# fpga-power-outside.net
KiCad netlist of a schematic drawn in Altium Designer
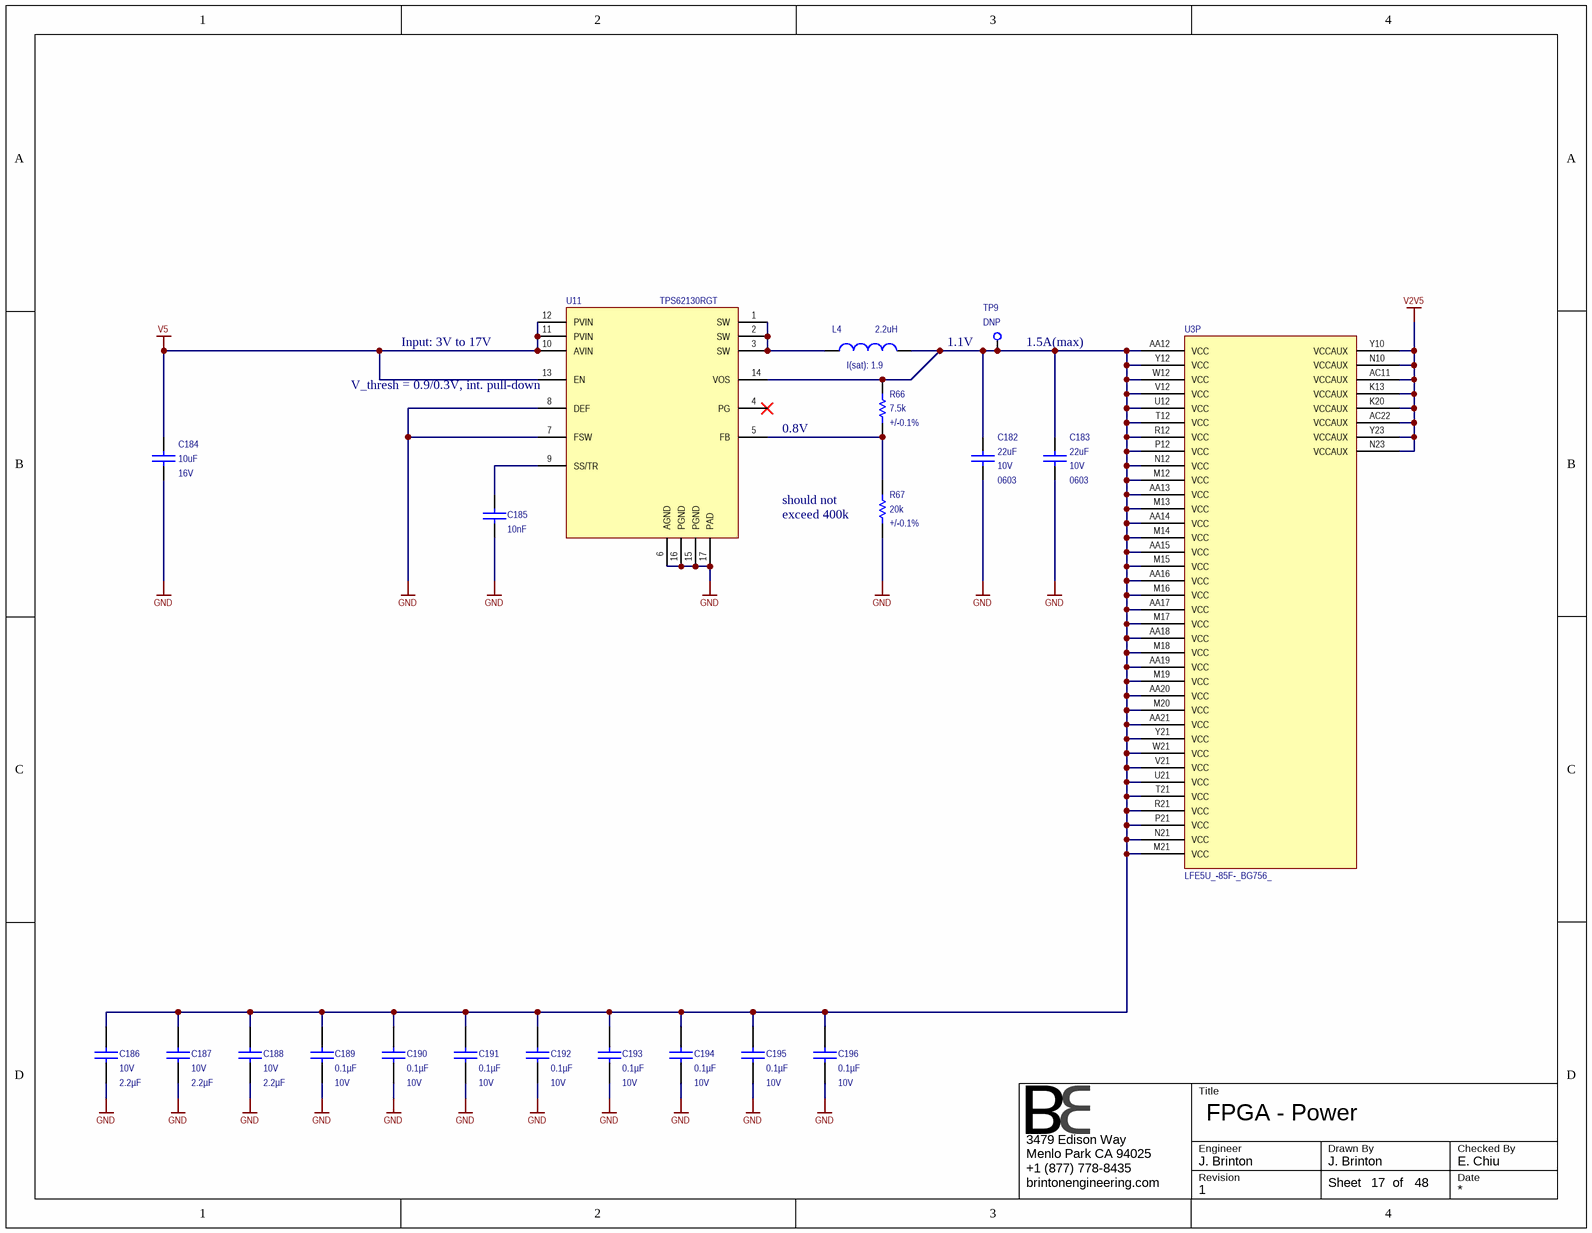
[diagram p0: fpga-power-outside.SchDoc]

(export (version "E")
  (design (tool "Eeschema 10.0.6"))
  (components
    (comp (ref "C182")
      (value "22uF")
      (footprint "0603")
      (description "Ceramic Capacitor 22uF +/-20% 10V X5R SMD 0603")
      (fields
        (field (name "MANUFACTURER") "TDK Corporation")
        (field (name "TOLERANCE") "+/-20%")
        (field (name "VOLTAGE") "10V")
      )
      (libsource (lib "generic") (part "CAP"))
    )
    (comp (ref "C183")
      (value "22uF")
      (footprint "0603")
      (description "Ceramic Capacitor 22uF +/-20% 10V X5R SMD 0603")
      (fields
        (field (name "MANUFACTURER") "TDK Corporation")
        (field (name "TOLERANCE") "+/-20%")
        (field (name "VOLTAGE") "10V")
      )
      (libsource (lib "generic") (part "CAP"))
    )
    (comp (ref "C184")
      (value "10uF")
      (footprint "0603")
      (description "Ceramic Capacitor 10uF +/-20% 16V X5R 0603")
      (fields
        (field (name "MANUFACTURER") "Taiyo Yuden")
        (field (name "VOLTAGE") "16V")
        (field (name "Comment") "CAP 10UF 0603")
      )
      (libsource (lib "") (part "CAP_1"))
    )
    (comp (ref "C185")
      (value "10nF")
      (footprint "0201")
      (description "Ceramic Capacitor 10nF +/-10% 10V X5R 0201")
      (fields (field (name "MANUFACTURER") "TDK Corporation") (field (name "VOLTAGE") "10V"))
      (libsource (lib "") (part "CAP_1"))
    )
    (comp (ref "C186")
      (value "GRM188R71A225KE15D")
      (footprint "CAPC1608X90N")
      (description "CAP CER 2.2UF 10V 10% X7R 0603")
      (fields
        (field (name "MANUFACTURER") "Murata Electronics North America")
        (field (name "TOLERANCE") "±10%")
        (field (name "VOLTAGE - RATED") "10V")
        (field (name "CAPACITANCE") "2.2µF")
      )
      (libsource (lib "murata") (part "GRM188R71A225KE15D"))
    )
    (comp (ref "C187")
      (value "GRM188R71A225KE15D")
      (footprint "CAPC1608X90N")
      (description "CAP CER 2.2UF 10V 10% X7R 0603")
      (fields
        (field (name "MANUFACTURER") "Murata Electronics North America")
        (field (name "TOLERANCE") "±10%")
        (field (name "VOLTAGE - RATED") "10V")
        (field (name "CAPACITANCE") "2.2µF")
      )
      (libsource (lib "murata") (part "GRM188R71A225KE15D"))
    )
    (comp (ref "C188")
      (value "GRM188R71A225KE15D")
      (footprint "CAPC1608X90N")
      (description "CAP CER 2.2UF 10V 10% X7R 0603")
      (fields
        (field (name "MANUFACTURER") "Murata Electronics North America")
        (field (name "TOLERANCE") "±10%")
        (field (name "VOLTAGE - RATED") "10V")
        (field (name "CAPACITANCE") "2.2µF")
      )
      (libsource (lib "murata") (part "GRM188R71A225KE15D"))
    )
    (comp (ref "C189")
      (value "GRM155R71A104KA01J")
      (footprint "CAPC1005X56N")
      (description "CAP CER 0.1UF 10V 10% X7R 0402")
      (fields
        (field (name "MANUFACTURER") "Murata Electronics North America")
        (field (name "TOLERANCE") "±10%")
        (field (name "CAPACITANCE") "0.1µF")
        (field (name "VOLTAGE - RATED") "10V")
      )
      (libsource (lib "murata") (part "GRM155R71A104KA01J"))
    )
    (comp (ref "C190")
      (value "GRM155R71A104KA01J")
      (footprint "CAPC1005X56N")
      (description "CAP CER 0.1UF 10V 10% X7R 0402")
      (fields
        (field (name "MANUFACTURER") "Murata Electronics North America")
        (field (name "TOLERANCE") "±10%")
        (field (name "CAPACITANCE") "0.1µF")
        (field (name "VOLTAGE - RATED") "10V")
      )
      (libsource (lib "murata") (part "GRM155R71A104KA01J"))
    )
    (comp (ref "C191")
      (value "GRM155R71A104KA01J")
      (footprint "CAPC1005X56N")
      (description "CAP CER 0.1UF 10V 10% X7R 0402")
      (fields
        (field (name "MANUFACTURER") "Murata Electronics North America")
        (field (name "TOLERANCE") "±10%")
        (field (name "CAPACITANCE") "0.1µF")
        (field (name "VOLTAGE - RATED") "10V")
      )
      (libsource (lib "murata") (part "GRM155R71A104KA01J"))
    )
    (comp (ref "C192")
      (value "GRM155R71A104KA01J")
      (footprint "CAPC1005X56N")
      (description "CAP CER 0.1UF 10V 10% X7R 0402")
      (fields
        (field (name "MANUFACTURER") "Murata Electronics North America")
        (field (name "TOLERANCE") "±10%")
        (field (name "CAPACITANCE") "0.1µF")
        (field (name "VOLTAGE - RATED") "10V")
      )
      (libsource (lib "murata") (part "GRM155R71A104KA01J"))
    )
    (comp (ref "C193")
      (value "GRM155R71A104KA01J")
      (footprint "CAPC1005X56N")
      (description "CAP CER 0.1UF 10V 10% X7R 0402")
      (fields
        (field (name "MANUFACTURER") "Murata Electronics North America")
        (field (name "TOLERANCE") "±10%")
        (field (name "CAPACITANCE") "0.1µF")
        (field (name "VOLTAGE - RATED") "10V")
      )
      (libsource (lib "murata") (part "GRM155R71A104KA01J"))
    )
    (comp (ref "C194")
      (value "GRM155R71A104KA01J")
      (footprint "CAPC1005X56N")
      (description "CAP CER 0.1UF 10V 10% X7R 0402")
      (fields
        (field (name "MANUFACTURER") "Murata Electronics North America")
        (field (name "TOLERANCE") "±10%")
        (field (name "CAPACITANCE") "0.1µF")
        (field (name "VOLTAGE - RATED") "10V")
      )
      (libsource (lib "murata") (part "GRM155R71A104KA01J"))
    )
    (comp (ref "C195")
      (value "GRM155R71A104KA01J")
      (footprint "CAPC1005X56N")
      (description "CAP CER 0.1UF 10V 10% X7R 0402")
      (fields
        (field (name "MANUFACTURER") "Murata Electronics North America")
        (field (name "TOLERANCE") "±10%")
        (field (name "CAPACITANCE") "0.1µF")
        (field (name "VOLTAGE - RATED") "10V")
      )
      (libsource (lib "murata") (part "GRM155R71A104KA01J"))
    )
    (comp (ref "C196")
      (value "GRM155R71A104KA01J")
      (footprint "CAPC1005X56N")
      (description "CAP CER 0.1UF 10V 10% X7R 0402")
      (fields
        (field (name "MANUFACTURER") "Murata Electronics North America")
        (field (name "TOLERANCE") "±10%")
        (field (name "CAPACITANCE") "0.1µF")
        (field (name "VOLTAGE - RATED") "10V")
      )
      (libsource (lib "murata") (part "GRM155R71A104KA01J"))
    )
    (comp (ref "L4")
      (value "2.2uH")
      (footprint "ASPI-3010FS")
      (description "Wirewound Inductor 2.2uH +/-20% 1.9A SMD 2518")
      (fields
        (field (name "MANUFACTURER") "Abracon")
        (field (name "I(SAT)") "1.9")
        (field (name "Comment") "ASPI-0310FS-2R2M-T2")
      )
      (libsource (lib "CamBoard_Pico_70.19K") (part "COIL"))
    )
    (comp (ref "R66")
      (value "7.5k")
      (footprint "RESC1608X55N")
      (description "Thick Film Resistor 7.5k Ohms +/-0.1% 0.1W 75V SMD 0603")
      (fields
        (field (name "TOLERANCE") "+/-0.1%")
        (field (name "MANUFACTURER") "Panasonic - ECG")
        (field (name "VOLTAGE") "75V")
      )
      (libsource (lib "brinton") (part "RES"))
    )
    (comp (ref "R67")
      (value "20k")
      (footprint "RESC1608X55N")
      (description "Thick Film Resistor 20k Ohms +/-0.1% 0.1W 75V SMD 0603")
      (fields
        (field (name "TOLERANCE") "+/-0.1%")
        (field (name "MANUFACTURER") "Panasonic - ECG")
        (field (name "VOLTAGE") "75V")
      )
      (libsource (lib "brinton") (part "RES"))
    )
    (comp (ref "TP9")
      (value "TEST_POINT")
      (footprint "TEST_POINT")
      (description "Thruhole Miniature Test Point")
      (fields (field (name "MANUFACTURER") "Keystone Electronics Corp") (field (name "DO NOT PLACE") "DNP"))
      (libsource (lib "generic") (part "TEST_POINT"))
    )
    (comp (ref "U3")
      (value "LFE5U_-85F-_BG756_")
      (footprint "lattice:caBGA756")
      (description "ECP5 FPGA, 85k LUT, 756-caBGA")
      (fields (field (name "MANUFACTURER") "Lattice Semiconductor"))
      (libsource (lib "lattice") (part "LFE5U_-85F-_BG756_"))
    )
    (comp (ref "U11")
      (value "TPS62130RGT")
      (footprint "S-PQFP-8N")
      (description "3-17V 3A Step-Down Converter VQFN")
      (fields (field (name "MANUFACTURER") "Texas Instruments"))
      (libsource (lib "ti") (part "TPS62130RGT"))
    )
  )
  (nets
    (net (code "1") (name "GND") (class "Default")
      (node (ref "C182") (pin "1") (pinfunction "1_1") (pintype "passive"))
      (node (ref "C183") (pin "1") (pinfunction "1_1") (pintype "passive"))
      (node (ref "C184") (pin "1") (pinfunction "1_1") (pintype "passive"))
      (node (ref "C185") (pin "2") (pinfunction "2_2") (pintype "passive"))
      (node (ref "C186") (pin "1") (pinfunction "1_1") (pintype "passive"))
      (node (ref "C187") (pin "1") (pinfunction "1_1") (pintype "passive"))
      (node (ref "C188") (pin "1") (pinfunction "1_1") (pintype "passive"))
      (node (ref "C189") (pin "1") (pinfunction "1_1") (pintype "passive"))
      (node (ref "C190") (pin "1") (pinfunction "1_1") (pintype "passive"))
      (node (ref "C191") (pin "1") (pinfunction "1_1") (pintype "passive"))
      (node (ref "C192") (pin "1") (pinfunction "1_1") (pintype "passive"))
      (node (ref "C193") (pin "1") (pinfunction "1_1") (pintype "passive"))
      (node (ref "C194") (pin "1") (pinfunction "1_1") (pintype "passive"))
      (node (ref "C195") (pin "1") (pinfunction "1_1") (pintype "passive"))
      (node (ref "C196") (pin "1") (pinfunction "1_1") (pintype "passive"))
      (node (ref "R67") (pin "1") (pinfunction "1_1") (pintype "passive"))
      (node (ref "U11") (pin "15") (pinfunction "PGND_15") (pintype "passive"))
      (node (ref "U11") (pin "16") (pinfunction "PGND_16") (pintype "passive"))
      (node (ref "U11") (pin "17") (pinfunction "PAD_17") (pintype "passive"))
      (node (ref "U11") (pin "6") (pinfunction "AGND_6") (pintype "passive"))
      (node (ref "U11") (pin "7") (pinfunction "FSW_7") (pintype "passive"))
      (node (ref "U11") (pin "8") (pinfunction "DEF_8") (pintype "passive"))
    )
    (net (code "2") (name "Net-(L4-Pad1)") (class "Default")
      (node (ref "L4") (pin "1") (pinfunction "1_1") (pintype "passive"))
      (node (ref "U11") (pin "1") (pinfunction "SW_1") (pintype "passive"))
      (node (ref "U11") (pin "2") (pinfunction "SW_2") (pintype "passive"))
      (node (ref "U11") (pin "3") (pinfunction "SW_3") (pintype "passive"))
    )
    (net (code "3") (name "Net-(U11-FB)") (class "Default")
      (node (ref "R66") (pin "1") (pinfunction "1_1") (pintype "passive"))
      (node (ref "R67") (pin "2") (pinfunction "2_2") (pintype "passive"))
      (node (ref "U11") (pin "5") (pinfunction "FB_5") (pintype "passive"))
    )
    (net (code "4") (name "Net-(U11-SS{slash}TR)") (class "Default")
      (node (ref "C185") (pin "1") (pinfunction "1_1") (pintype "passive"))
      (node (ref "U11") (pin "9") (pinfunction "SS/TR_9") (pintype "passive"))
    )
    (net (code "5") (name "Net-(U11-VOS)") (class "Default")
      (node (ref "C182") (pin "2") (pinfunction "2_2") (pintype "passive"))
      (node (ref "C183") (pin "2") (pinfunction "2_2") (pintype "passive"))
      (node (ref "C186") (pin "2") (pinfunction "2_2") (pintype "passive"))
      (node (ref "C187") (pin "2") (pinfunction "2_2") (pintype "passive"))
      (node (ref "C188") (pin "2") (pinfunction "2_2") (pintype "passive"))
      (node (ref "C189") (pin "2") (pinfunction "2_2") (pintype "passive"))
      (node (ref "C190") (pin "2") (pinfunction "2_2") (pintype "passive"))
      (node (ref "C191") (pin "2") (pinfunction "2_2") (pintype "passive"))
      (node (ref "C192") (pin "2") (pinfunction "2_2") (pintype "passive"))
      (node (ref "C193") (pin "2") (pinfunction "2_2") (pintype "passive"))
      (node (ref "C194") (pin "2") (pinfunction "2_2") (pintype "passive"))
      (node (ref "C195") (pin "2") (pinfunction "2_2") (pintype "passive"))
      (node (ref "C196") (pin "2") (pinfunction "2_2") (pintype "passive"))
      (node (ref "L4") (pin "2") (pinfunction "2_2") (pintype "passive"))
      (node (ref "R66") (pin "2") (pinfunction "2_2") (pintype "passive"))
      (node (ref "TP9") (pin "1") (pinfunction "1_1") (pintype "passive"))
      (node (ref "U11") (pin "14") (pinfunction "VOS_14") (pintype "passive"))
      (node (ref "U3") (pin "AA12") (pinfunction "VCC_AA12") (pintype "power_in"))
      (node (ref "U3") (pin "AA13") (pinfunction "VCC_AA13") (pintype "power_in"))
      (node (ref "U3") (pin "AA14") (pinfunction "VCC_AA14") (pintype "power_in"))
      (node (ref "U3") (pin "AA15") (pinfunction "VCC_AA15") (pintype "power_in"))
      (node (ref "U3") (pin "AA16") (pinfunction "VCC_AA16") (pintype "power_in"))
      (node (ref "U3") (pin "AA17") (pinfunction "VCC_AA17") (pintype "power_in"))
      (node (ref "U3") (pin "AA18") (pinfunction "VCC_AA18") (pintype "power_in"))
      (node (ref "U3") (pin "AA19") (pinfunction "VCC_AA19") (pintype "power_in"))
      (node (ref "U3") (pin "AA20") (pinfunction "VCC_AA20") (pintype "power_in"))
      (node (ref "U3") (pin "AA21") (pinfunction "VCC_AA21") (pintype "power_in"))
      (node (ref "U3") (pin "M12") (pinfunction "VCC_M12") (pintype "power_in"))
      (node (ref "U3") (pin "M13") (pinfunction "VCC_M13") (pintype "power_in"))
      (node (ref "U3") (pin "M14") (pinfunction "VCC_M14") (pintype "power_in"))
      (node (ref "U3") (pin "M15") (pinfunction "VCC_M15") (pintype "power_in"))
      (node (ref "U3") (pin "M16") (pinfunction "VCC_M16") (pintype "power_in"))
      (node (ref "U3") (pin "M17") (pinfunction "VCC_M17") (pintype "power_in"))
      (node (ref "U3") (pin "M18") (pinfunction "VCC_M18") (pintype "power_in"))
      (node (ref "U3") (pin "M19") (pinfunction "VCC_M19") (pintype "power_in"))
      (node (ref "U3") (pin "M20") (pinfunction "VCC_M20") (pintype "power_in"))
      (node (ref "U3") (pin "M21") (pinfunction "VCC_M21") (pintype "power_in"))
      (node (ref "U3") (pin "N12") (pinfunction "VCC_N12") (pintype "power_in"))
      (node (ref "U3") (pin "N21") (pinfunction "VCC_N21") (pintype "power_in"))
      (node (ref "U3") (pin "P12") (pinfunction "VCC_P12") (pintype "power_in"))
      (node (ref "U3") (pin "P21") (pinfunction "VCC_P21") (pintype "power_in"))
      (node (ref "U3") (pin "R12") (pinfunction "VCC_R12") (pintype "power_in"))
      (node (ref "U3") (pin "R21") (pinfunction "VCC_R21") (pintype "power_in"))
      (node (ref "U3") (pin "T12") (pinfunction "VCC_T12") (pintype "power_in"))
      (node (ref "U3") (pin "T21") (pinfunction "VCC_T21") (pintype "power_in"))
      (node (ref "U3") (pin "U12") (pinfunction "VCC_U12") (pintype "power_in"))
      (node (ref "U3") (pin "U21") (pinfunction "VCC_U21") (pintype "power_in"))
      (node (ref "U3") (pin "V12") (pinfunction "VCC_V12") (pintype "power_in"))
      (node (ref "U3") (pin "V21") (pinfunction "VCC_V21") (pintype "power_in"))
      (node (ref "U3") (pin "W12") (pinfunction "VCC_W12") (pintype "power_in"))
      (node (ref "U3") (pin "W21") (pinfunction "VCC_W21") (pintype "power_in"))
      (node (ref "U3") (pin "Y12") (pinfunction "VCC_Y12") (pintype "power_in"))
      (node (ref "U3") (pin "Y21") (pinfunction "VCC_Y21") (pintype "power_in"))
    )
    (net (code "6") (name "V2V5") (class "Default")
      (node (ref "U3") (pin "AC11") (pinfunction "VCCAUX_AC11") (pintype "power_in"))
      (node (ref "U3") (pin "AC22") (pinfunction "VCCAUX_AC22") (pintype "power_in"))
      (node (ref "U3") (pin "K13") (pinfunction "VCCAUX_K13") (pintype "power_in"))
      (node (ref "U3") (pin "K20") (pinfunction "VCCAUX_K20") (pintype "power_in"))
      (node (ref "U3") (pin "N10") (pinfunction "VCCAUX_N10") (pintype "power_in"))
      (node (ref "U3") (pin "N23") (pinfunction "VCCAUX_N23") (pintype "power_in"))
      (node (ref "U3") (pin "Y10") (pinfunction "VCCAUX_Y10") (pintype "power_in"))
      (node (ref "U3") (pin "Y23") (pinfunction "VCCAUX_Y23") (pintype "power_in"))
    )
    (net (code "7") (name "V5") (class "Default")
      (node (ref "C184") (pin "2") (pinfunction "2_2") (pintype "passive"))
      (node (ref "U11") (pin "10") (pinfunction "AVIN_10") (pintype "passive"))
      (node (ref "U11") (pin "11") (pinfunction "PVIN_11") (pintype "passive"))
      (node (ref "U11") (pin "12") (pinfunction "PVIN_12") (pintype "passive"))
      (node (ref "U11") (pin "13") (pinfunction "EN_13") (pintype "passive"))
    )
    (net (code "8") (name "unconnected-(U11-PG-Pad4)") (class "Default")
      (node (ref "U11") (pin "4") (pinfunction "PG_4") (pintype "passive+no_connect"))
    )
  )
)
